# fastADCs.net
KiCad netlist of a schematic drawn in Altium Designer
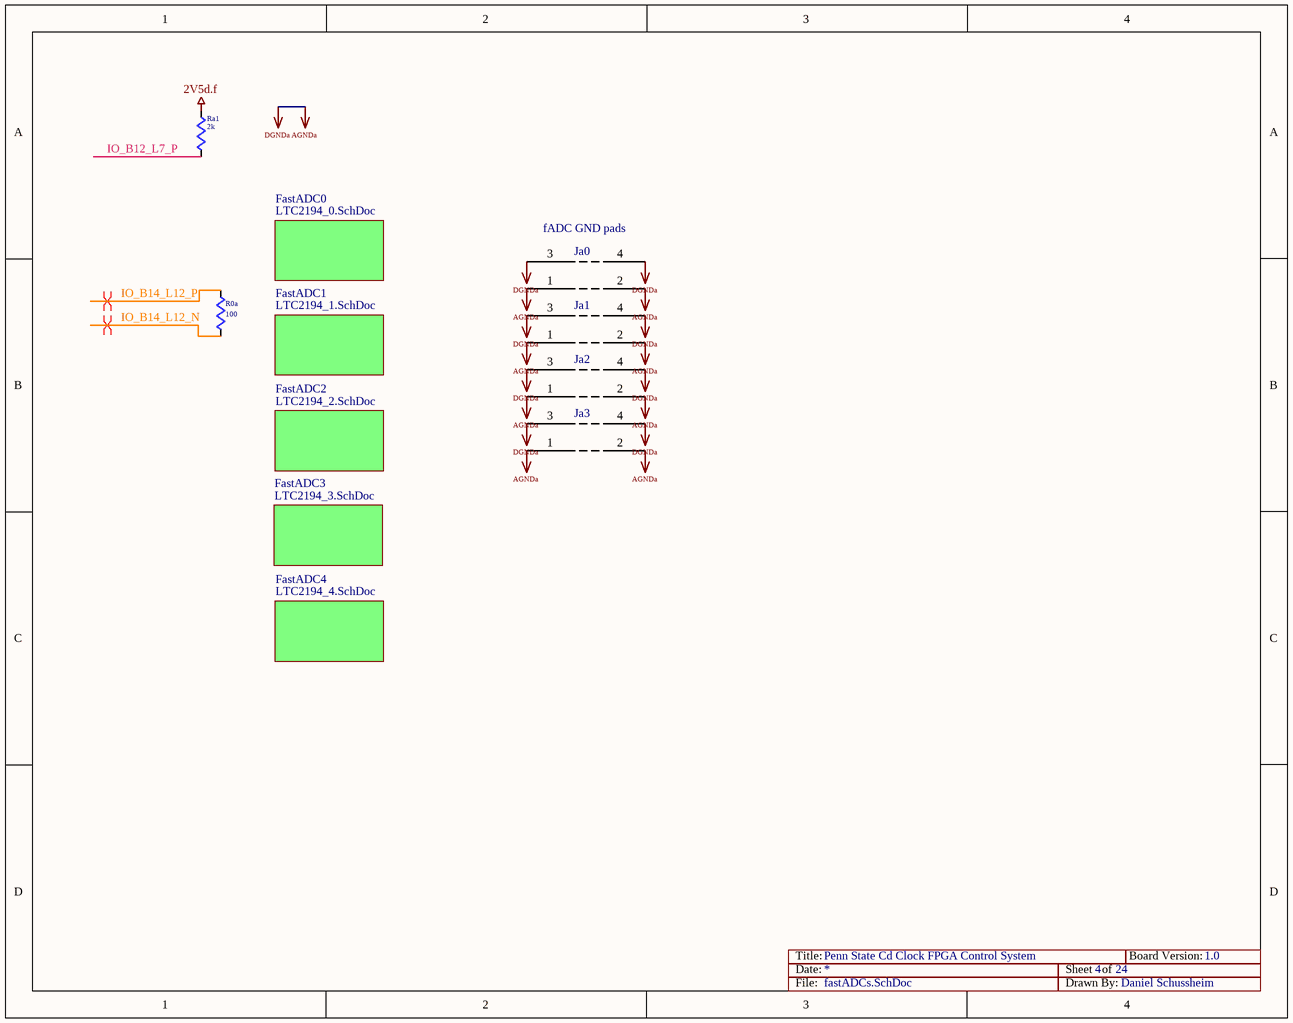
[diagram p0: fastADCs.SchDoc]

(export (version "E")
  (design (tool "Eeschema 10.0.6"))
  (components
    (comp (ref "Ja0")
      (value "fADC GND pads")
      (footprint "FADC_GND_CONN")
      (libsource (lib "Mercury_AD_BaseBoard_SCHLIB") (part "fADC GND pads"))
    )
    (comp (ref "Ja1")
      (value "fADC GND pads")
      (footprint "FADC_GND_CONN")
      (libsource (lib "Mercury_AD_BaseBoard_SCHLIB") (part "fADC GND pads"))
    )
    (comp (ref "Ja2")
      (value "fADC GND pads")
      (footprint "FADC_GND_CONN")
      (libsource (lib "Mercury_AD_BaseBoard_SCHLIB") (part "fADC GND pads"))
    )
    (comp (ref "Ja3")
      (value "fADC GND pads")
      (footprint "FADC_GND_CONN")
      (libsource (lib "Mercury_AD_BaseBoard_SCHLIB") (part "fADC GND pads"))
    )
    (comp (ref "R0a")
      (value "100")
      (footprint "0402")
      (libsource (lib "Mercury_AD_BaseBoard_SCHLIB") (part "RES"))
    )
    (comp (ref "Ra1")
      (value "2k")
      (footprint "0603")
      (libsource (lib "Mercury_AD_BaseBoard_SCHLIB") (part "RES"))
    )
  )
  (nets
    (net (code "1") (name "/IO_B12_L7_P") (class "Default") (node (ref "Ra1") (pin "2") (pintype "passive")))
    (net (code "2") (name "/IO_B14_L12_N") (class "Default") (node (ref "R0a") (pin "2") (pintype "passive")))
    (net (code "3") (name "/IO_B14_L12_P") (class "Default") (node (ref "R0a") (pin "1") (pintype "passive")))
    (net (code "4") (name "2V5d.f") (class "Default") (node (ref "Ra1") (pin "1") (pintype "passive")))
    (net (code "5") (name "AGNDa") (class "Default")
      (node (ref "Ja0") (pin "1") (pinfunction "1_1") (pintype "passive"))
      (node (ref "Ja0") (pin "2") (pinfunction "2_2") (pintype "passive"))
      (node (ref "Ja0") (pin "3") (pinfunction "3_3") (pintype "passive"))
      (node (ref "Ja0") (pin "4") (pinfunction "4_4") (pintype "passive"))
      (node (ref "Ja1") (pin "1") (pinfunction "1_1") (pintype "passive"))
      (node (ref "Ja1") (pin "2") (pinfunction "2_2") (pintype "passive"))
      (node (ref "Ja1") (pin "3") (pinfunction "3_3") (pintype "passive"))
      (node (ref "Ja1") (pin "4") (pinfunction "4_4") (pintype "passive"))
      (node (ref "Ja2") (pin "1") (pinfunction "1_1") (pintype "passive"))
      (node (ref "Ja2") (pin "2") (pinfunction "2_2") (pintype "passive"))
      (node (ref "Ja2") (pin "3") (pinfunction "3_3") (pintype "passive"))
      (node (ref "Ja2") (pin "4") (pinfunction "4_4") (pintype "passive"))
      (node (ref "Ja3") (pin "1") (pinfunction "1_1") (pintype "passive"))
      (node (ref "Ja3") (pin "2") (pinfunction "2_2") (pintype "passive"))
      (node (ref "Ja3") (pin "3") (pinfunction "3_3") (pintype "passive"))
      (node (ref "Ja3") (pin "4") (pinfunction "4_4") (pintype "passive"))
    )
  )
)
